# ANA.net
KiCad netlist of a schematic drawn in Altium Designer
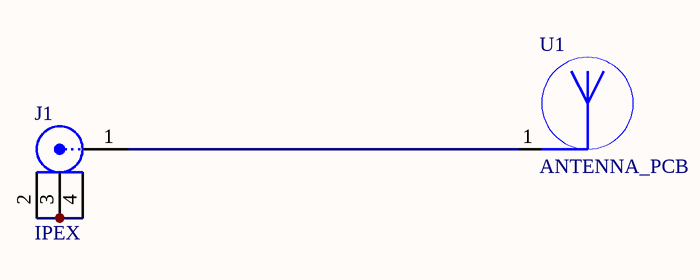
[diagram p0: ANA.SchDoc]

(export (version "E")
  (design (tool "Eeschema 10.0.6"))
  (components
    (comp (ref "J1")
      (value "IPEX")
      (footprint "molex-73412")
      (description "RF同轴连接器（天线座）")
      (fields (field (name "MANUFACTURER") "MOLEX"))
      (libsource (lib "J") (part "73412-0110"))
    )
    (comp (ref "U1")
      (value "ANTENNA_PCB")
      (footprint "ANTENNA_DN024N")
      (libsource (lib "RF") (part "ANTENNA_PCB"))
    )
  )
  (nets
    (net (code "1") (name "Net-(J1-Pad1)") (class "Default")
      (node (ref "J1") (pin "1") (pinfunction "1_1") (pintype "passive"))
      (node (ref "U1") (pin "1") (pinfunction "1_1") (pintype "passive"))
    )
    (net (code "2") (name "Net-(J1-Pad2)") (class "Default")
      (node (ref "J1") (pin "2") (pinfunction "2_2") (pintype "passive"))
      (node (ref "J1") (pin "3") (pinfunction "3_3") (pintype "passive"))
      (node (ref "J1") (pin "4") (pinfunction "4_4") (pintype "passive"))
    )
  )
)
